# fp2.net
KiCad netlist of a schematic drawn in EAGLE
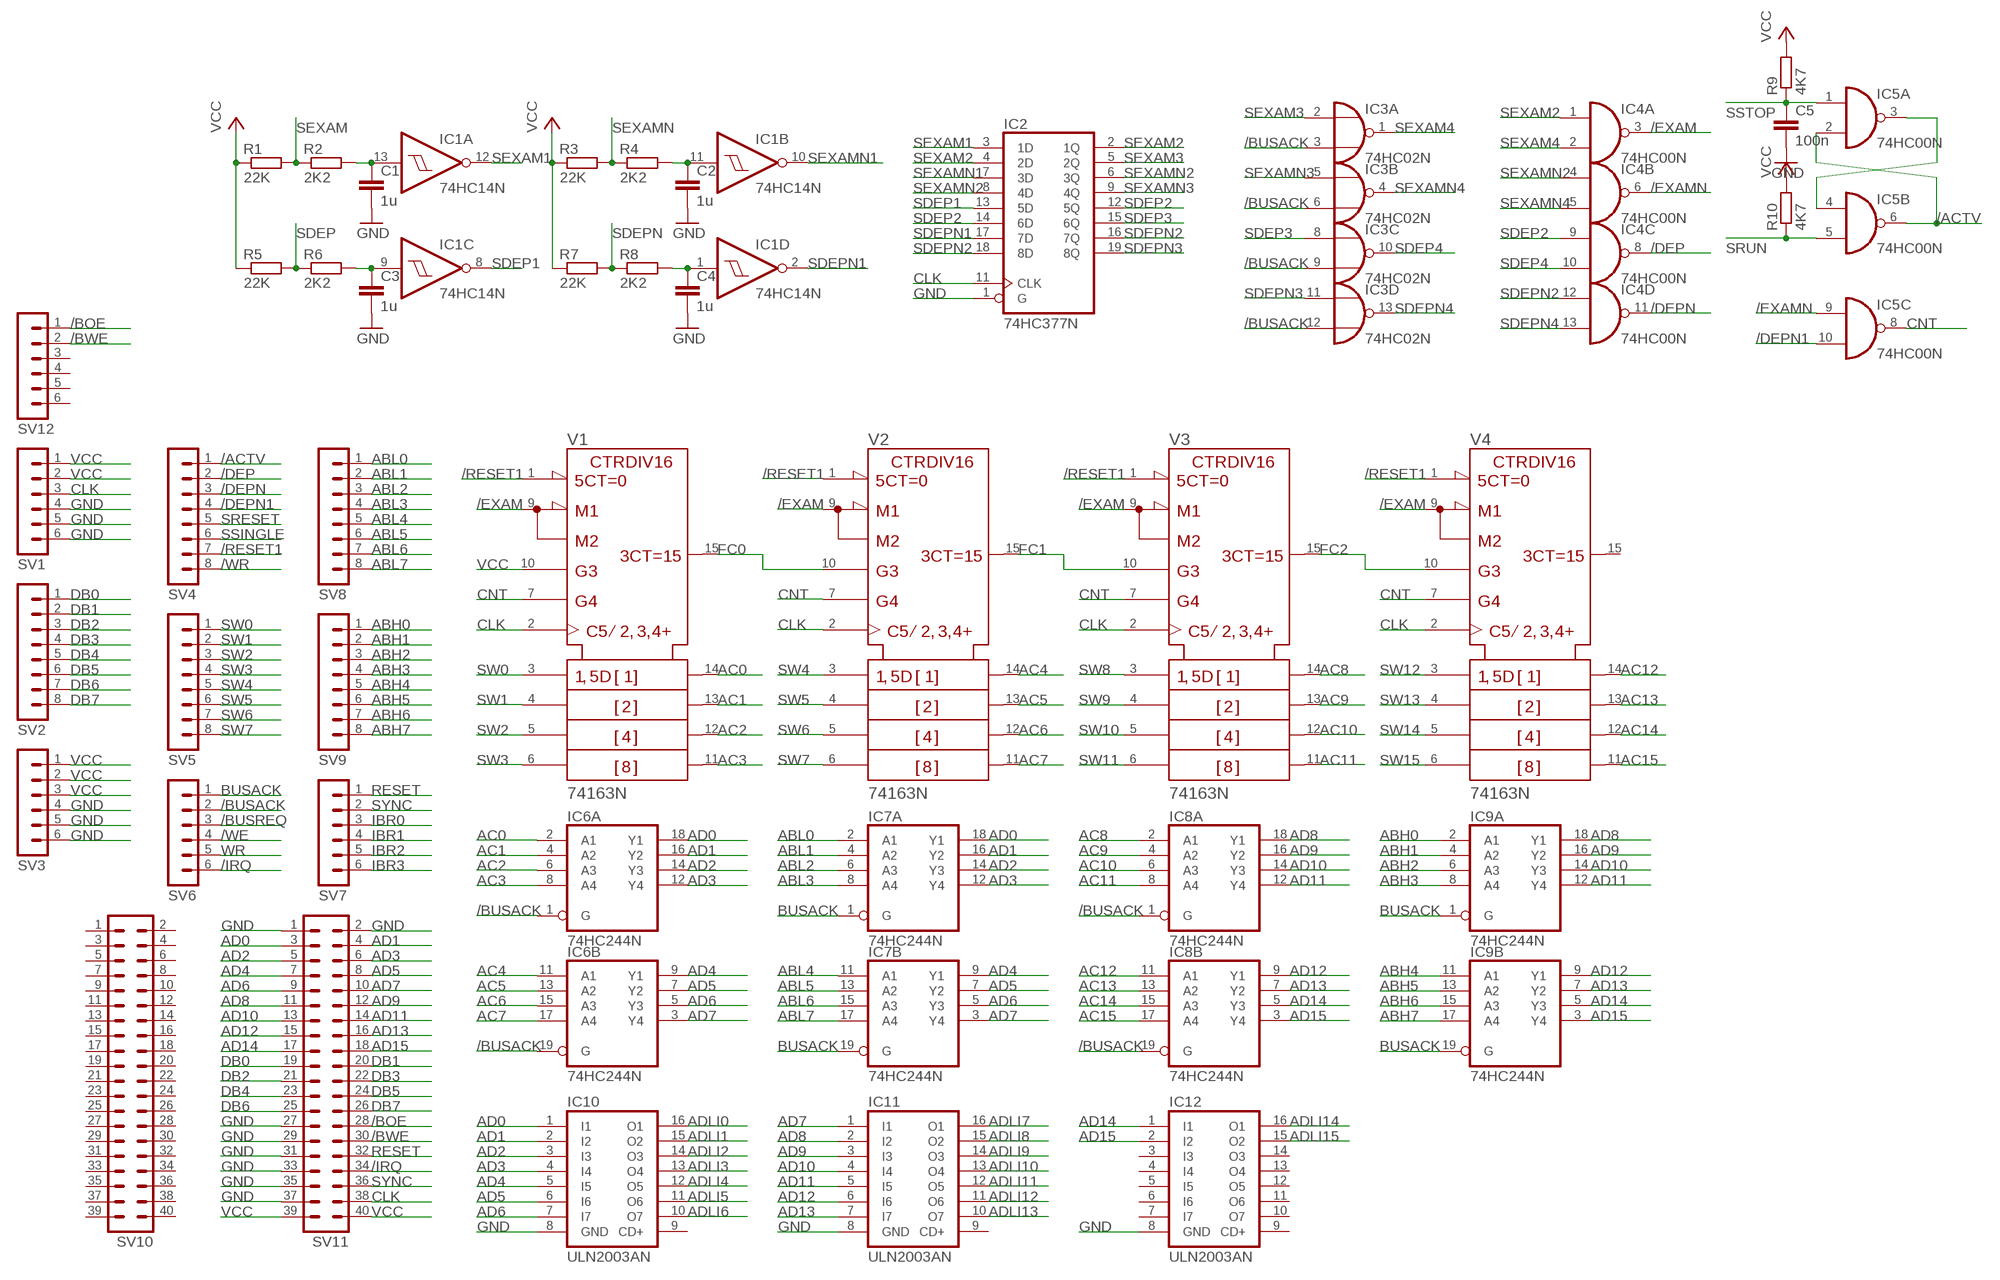
[diagram p0: schematic, sheet 1]

(export (version "E")
  (design (tool "Eeschema 10.0.6"))
  (components
    (comp (ref "C1")
      (value "1u")
      (footprint "eagle-import:C025-024X044")
      (libsource (lib "eagle-import") (part "C-EU025-024X044"))
    )
    (comp (ref "C2")
      (value "1u")
      (footprint "eagle-import:C025-024X044")
      (libsource (lib "eagle-import") (part "C-EU025-024X044"))
    )
    (comp (ref "C3")
      (value "1u")
      (footprint "eagle-import:C025-024X044")
      (libsource (lib "eagle-import") (part "C-EU025-024X044"))
    )
    (comp (ref "C4")
      (value "1u")
      (footprint "eagle-import:C025-024X044")
      (libsource (lib "eagle-import") (part "C-EU025-024X044"))
    )
    (comp (ref "C5")
      (value "100n")
      (footprint "eagle-import:C025-024X044")
      (libsource (lib "eagle-import") (part "C-EU025-024X044"))
    )
    (comp (ref "IC1")
      (value "74HC14N")
      (footprint "eagle-import:DIL14")
      (libsource (lib "eagle-import") (part "7414NHC"))
    )
    (comp (ref "IC2")
      (value "74HC377N")
      (footprint "eagle-import:DIL20")
      (libsource (lib "eagle-import") (part "74377NHC"))
    )
    (comp (ref "IC3")
      (value "74HC02N")
      (footprint "eagle-import:DIL14")
      (libsource (lib "eagle-import") (part "7402NHC"))
    )
    (comp (ref "IC4")
      (value "74HC00N")
      (footprint "eagle-import:DIL14")
      (libsource (lib "eagle-import") (part "7400NHC"))
    )
    (comp (ref "IC5")
      (value "74HC00N")
      (footprint "eagle-import:DIL14")
      (libsource (lib "eagle-import") (part "7400NHC"))
    )
    (comp (ref "IC6")
      (value "74HC244N")
      (footprint "eagle-import:DIL20")
      (libsource (lib "eagle-import") (part "74244NHC"))
    )
    (comp (ref "IC7")
      (value "74HC244N")
      (footprint "eagle-import:DIL20")
      (libsource (lib "eagle-import") (part "74244NHC"))
    )
    (comp (ref "IC8")
      (value "74HC244N")
      (footprint "eagle-import:DIL20")
      (libsource (lib "eagle-import") (part "74244NHC"))
    )
    (comp (ref "IC9")
      (value "74HC244N")
      (footprint "eagle-import:DIL20")
      (libsource (lib "eagle-import") (part "74244NHC"))
    )
    (comp (ref "IC10")
      (value "ULN2003AN")
      (footprint "eagle-import:DIL16")
      (libsource (lib "eagle-import") (part "ULN2003AN"))
    )
    (comp (ref "IC11")
      (value "ULN2003AN")
      (footprint "eagle-import:DIL16")
      (libsource (lib "eagle-import") (part "ULN2003AN"))
    )
    (comp (ref "IC12")
      (value "ULN2003AN")
      (footprint "eagle-import:DIL16")
      (libsource (lib "eagle-import") (part "ULN2003AN"))
    )
    (comp (ref "R1")
      (value "22K")
      (footprint "eagle-import:0204_7")
      (libsource (lib "eagle-import") (part "R-EU_0204/7"))
    )
    (comp (ref "R2")
      (value "2K2")
      (footprint "eagle-import:0204_7")
      (libsource (lib "eagle-import") (part "R-EU_0204/7"))
    )
    (comp (ref "R3")
      (value "22K")
      (footprint "eagle-import:0204_7")
      (libsource (lib "eagle-import") (part "R-EU_0204/7"))
    )
    (comp (ref "R4")
      (value "2K2")
      (footprint "eagle-import:0204_7")
      (libsource (lib "eagle-import") (part "R-EU_0204/7"))
    )
    (comp (ref "R5")
      (value "22K")
      (footprint "eagle-import:0204_7")
      (libsource (lib "eagle-import") (part "R-EU_0204/7"))
    )
    (comp (ref "R6")
      (value "2K2")
      (footprint "eagle-import:0204_7")
      (libsource (lib "eagle-import") (part "R-EU_0204/7"))
    )
    (comp (ref "R7")
      (value "22K")
      (footprint "eagle-import:0204_7")
      (libsource (lib "eagle-import") (part "R-EU_0204/7"))
    )
    (comp (ref "R8")
      (value "2K2")
      (footprint "eagle-import:0204_7")
      (libsource (lib "eagle-import") (part "R-EU_0204/7"))
    )
    (comp (ref "R9")
      (value "4K7")
      (footprint "eagle-import:0204_7")
      (libsource (lib "eagle-import") (part "R-EU_0204/7"))
    )
    (comp (ref "R10")
      (value "4K7")
      (footprint "eagle-import:0204_7")
      (libsource (lib "eagle-import") (part "R-EU_0204/7"))
    )
    (comp (ref "SV1")
      (value "MA06-1")
      (footprint "eagle-import:MA06-1")
      (libsource (lib "eagle-import") (part "MA06-1"))
    )
    (comp (ref "SV2")
      (value "MA08-1")
      (footprint "eagle-import:MA08-1")
      (libsource (lib "eagle-import") (part "MA08-1"))
    )
    (comp (ref "SV3")
      (value "MA06-1")
      (footprint "eagle-import:MA06-1")
      (libsource (lib "eagle-import") (part "MA06-1"))
    )
    (comp (ref "SV4")
      (value "MA08-1")
      (footprint "eagle-import:MA08-1")
      (libsource (lib "eagle-import") (part "MA08-1"))
    )
    (comp (ref "SV5")
      (value "MA08-1")
      (footprint "eagle-import:MA08-1")
      (libsource (lib "eagle-import") (part "MA08-1"))
    )
    (comp (ref "SV6")
      (value "MA06-1")
      (footprint "eagle-import:MA06-1")
      (libsource (lib "eagle-import") (part "MA06-1"))
    )
    (comp (ref "SV7")
      (value "MA06-1")
      (footprint "eagle-import:MA06-1")
      (libsource (lib "eagle-import") (part "MA06-1"))
    )
    (comp (ref "SV8")
      (value "MA08-1")
      (footprint "eagle-import:MA08-1")
      (libsource (lib "eagle-import") (part "MA08-1"))
    )
    (comp (ref "SV9")
      (value "MA08-1")
      (footprint "eagle-import:MA08-1")
      (libsource (lib "eagle-import") (part "MA08-1"))
    )
    (comp (ref "SV10")
      (value "MA20-2")
      (footprint "eagle-import:MA20-2")
      (libsource (lib "eagle-import") (part "MA20-2"))
    )
    (comp (ref "SV11")
      (value "MA20-2")
      (footprint "eagle-import:MA20-2")
      (libsource (lib "eagle-import") (part "MA20-2"))
    )
    (comp (ref "SV12")
      (value "MA06-1")
      (footprint "eagle-import:MA06-1")
      (libsource (lib "eagle-import") (part "MA06-1"))
    )
    (comp (ref "V1")
      (value "74163N")
      (footprint "eagle-import:DIL16")
      (libsource (lib "eagle-import") (part "74163N"))
    )
    (comp (ref "V2")
      (value "74163N")
      (footprint "eagle-import:DIL16")
      (libsource (lib "eagle-import") (part "74163N"))
    )
    (comp (ref "V3")
      (value "74163N")
      (footprint "eagle-import:DIL16")
      (libsource (lib "eagle-import") (part "74163N"))
    )
    (comp (ref "V4")
      (value "74163N")
      (footprint "eagle-import:DIL16")
      (libsource (lib "eagle-import") (part "74163N"))
    )
  )
  (nets
    (net (code "1") (name "/ABH0") (class "Default")
      (node (ref "IC9") (pin "2") (pinfunction "A1_2") (pintype "input"))
      (node (ref "SV9") (pin "1") (pinfunction "1_1") (pintype "passive"))
    )
    (net (code "2") (name "/ABH1") (class "Default")
      (node (ref "IC9") (pin "4") (pinfunction "A2_4") (pintype "input"))
      (node (ref "SV9") (pin "2") (pinfunction "2_2") (pintype "passive"))
    )
    (net (code "3") (name "/ABH2") (class "Default")
      (node (ref "IC9") (pin "6") (pinfunction "A3_6") (pintype "input"))
      (node (ref "SV9") (pin "3") (pinfunction "3_3") (pintype "passive"))
    )
    (net (code "4") (name "/ABH3") (class "Default")
      (node (ref "IC9") (pin "8") (pinfunction "A4_8") (pintype "input"))
      (node (ref "SV9") (pin "4") (pinfunction "4_4") (pintype "passive"))
    )
    (net (code "5") (name "/ABH4") (class "Default")
      (node (ref "IC9") (pin "11") (pinfunction "A1_11") (pintype "input"))
      (node (ref "SV9") (pin "5") (pinfunction "5_5") (pintype "passive"))
    )
    (net (code "6") (name "/ABH5") (class "Default")
      (node (ref "IC9") (pin "13") (pinfunction "A2_13") (pintype "input"))
      (node (ref "SV9") (pin "6") (pinfunction "6_6") (pintype "passive"))
    )
    (net (code "7") (name "/ABH6") (class "Default")
      (node (ref "IC9") (pin "15") (pinfunction "A3_15") (pintype "input"))
      (node (ref "SV9") (pin "7") (pinfunction "7_7") (pintype "passive"))
    )
    (net (code "8") (name "/ABH7") (class "Default")
      (node (ref "IC9") (pin "17") (pinfunction "A4_17") (pintype "input"))
      (node (ref "SV9") (pin "8") (pinfunction "8_8") (pintype "passive"))
    )
    (net (code "9") (name "/ABL0") (class "Default")
      (node (ref "IC7") (pin "2") (pinfunction "A1_2") (pintype "input"))
      (node (ref "SV8") (pin "1") (pinfunction "1_1") (pintype "passive"))
    )
    (net (code "10") (name "/ABL1") (class "Default")
      (node (ref "IC7") (pin "4") (pinfunction "A2_4") (pintype "input"))
      (node (ref "SV8") (pin "2") (pinfunction "2_2") (pintype "passive"))
    )
    (net (code "11") (name "/ABL2") (class "Default")
      (node (ref "IC7") (pin "6") (pinfunction "A3_6") (pintype "input"))
      (node (ref "SV8") (pin "3") (pinfunction "3_3") (pintype "passive"))
    )
    (net (code "12") (name "/ABL3") (class "Default")
      (node (ref "IC7") (pin "8") (pinfunction "A4_8") (pintype "input"))
      (node (ref "SV8") (pin "4") (pinfunction "4_4") (pintype "passive"))
    )
    (net (code "13") (name "/ABL4") (class "Default")
      (node (ref "IC7") (pin "11") (pinfunction "A1_11") (pintype "input"))
      (node (ref "SV8") (pin "5") (pinfunction "5_5") (pintype "passive"))
    )
    (net (code "14") (name "/ABL5") (class "Default")
      (node (ref "IC7") (pin "13") (pinfunction "A2_13") (pintype "input"))
      (node (ref "SV8") (pin "6") (pinfunction "6_6") (pintype "passive"))
    )
    (net (code "15") (name "/ABL6") (class "Default")
      (node (ref "IC7") (pin "15") (pinfunction "A3_15") (pintype "input"))
      (node (ref "SV8") (pin "7") (pinfunction "7_7") (pintype "passive"))
    )
    (net (code "16") (name "/ABL7") (class "Default")
      (node (ref "IC7") (pin "17") (pinfunction "A4_17") (pintype "input"))
      (node (ref "SV8") (pin "8") (pinfunction "8_8") (pintype "passive"))
    )
    (net (code "17") (name "/AC0") (class "Default")
      (node (ref "IC6") (pin "2") (pinfunction "A1_2") (pintype "input"))
      (node (ref "V1") (pin "14") (pinfunction "QA_14") (pintype "output"))
    )
    (net (code "18") (name "/AC1") (class "Default")
      (node (ref "IC6") (pin "4") (pinfunction "A2_4") (pintype "input"))
      (node (ref "V1") (pin "13") (pinfunction "QB_13") (pintype "output"))
    )
    (net (code "19") (name "/AC2") (class "Default")
      (node (ref "IC6") (pin "6") (pinfunction "A3_6") (pintype "input"))
      (node (ref "V1") (pin "12") (pinfunction "QC_12") (pintype "output"))
    )
    (net (code "20") (name "/AC3") (class "Default")
      (node (ref "IC6") (pin "8") (pinfunction "A4_8") (pintype "input"))
      (node (ref "V1") (pin "11") (pinfunction "QD_11") (pintype "output"))
    )
    (net (code "21") (name "/AC4") (class "Default")
      (node (ref "IC6") (pin "11") (pinfunction "A1_11") (pintype "input"))
      (node (ref "V2") (pin "14") (pinfunction "QA_14") (pintype "output"))
    )
    (net (code "22") (name "/AC5") (class "Default")
      (node (ref "IC6") (pin "13") (pinfunction "A2_13") (pintype "input"))
      (node (ref "V2") (pin "13") (pinfunction "QB_13") (pintype "output"))
    )
    (net (code "23") (name "/AC6") (class "Default")
      (node (ref "IC6") (pin "15") (pinfunction "A3_15") (pintype "input"))
      (node (ref "V2") (pin "12") (pinfunction "QC_12") (pintype "output"))
    )
    (net (code "24") (name "/AC7") (class "Default")
      (node (ref "IC6") (pin "17") (pinfunction "A4_17") (pintype "input"))
      (node (ref "V2") (pin "11") (pinfunction "QD_11") (pintype "output"))
    )
    (net (code "25") (name "/AC8") (class "Default")
      (node (ref "IC8") (pin "2") (pinfunction "A1_2") (pintype "input"))
      (node (ref "V3") (pin "14") (pinfunction "QA_14") (pintype "output"))
    )
    (net (code "26") (name "/AC9") (class "Default")
      (node (ref "IC8") (pin "4") (pinfunction "A2_4") (pintype "input"))
      (node (ref "V3") (pin "13") (pinfunction "QB_13") (pintype "output"))
    )
    (net (code "27") (name "/AC10") (class "Default")
      (node (ref "IC8") (pin "6") (pinfunction "A3_6") (pintype "input"))
      (node (ref "V3") (pin "12") (pinfunction "QC_12") (pintype "output"))
    )
    (net (code "28") (name "/AC11") (class "Default")
      (node (ref "IC8") (pin "8") (pinfunction "A4_8") (pintype "input"))
      (node (ref "V3") (pin "11") (pinfunction "QD_11") (pintype "output"))
    )
    (net (code "29") (name "/AC12") (class "Default")
      (node (ref "IC8") (pin "11") (pinfunction "A1_11") (pintype "input"))
      (node (ref "V4") (pin "14") (pinfunction "QA_14") (pintype "output"))
    )
    (net (code "30") (name "/AC13") (class "Default")
      (node (ref "IC8") (pin "13") (pinfunction "A2_13") (pintype "input"))
      (node (ref "V4") (pin "13") (pinfunction "QB_13") (pintype "output"))
    )
    (net (code "31") (name "/AC14") (class "Default")
      (node (ref "IC8") (pin "15") (pinfunction "A3_15") (pintype "input"))
      (node (ref "V4") (pin "12") (pinfunction "QC_12") (pintype "output"))
    )
    (net (code "32") (name "/AC15") (class "Default")
      (node (ref "IC8") (pin "17") (pinfunction "A4_17") (pintype "input"))
      (node (ref "V4") (pin "11") (pinfunction "QD_11") (pintype "output"))
    )
    (net (code "33") (name "/AD0") (class "Default")
      (node (ref "IC10") (pin "1") (pinfunction "I1_1") (pintype "input"))
      (node (ref "IC6") (pin "18") (pinfunction "Y1_18") (pintype "tri_state"))
      (node (ref "IC7") (pin "18") (pinfunction "Y1_18") (pintype "tri_state"))
      (node (ref "SV11") (pin "3") (pinfunction "3_3") (pintype "passive"))
    )
    (net (code "34") (name "/AD1") (class "Default")
      (node (ref "IC10") (pin "2") (pinfunction "I2_2") (pintype "input"))
      (node (ref "IC6") (pin "16") (pinfunction "Y2_16") (pintype "tri_state"))
      (node (ref "IC7") (pin "16") (pinfunction "Y2_16") (pintype "tri_state"))
      (node (ref "SV11") (pin "4") (pinfunction "4_4") (pintype "passive"))
    )
    (net (code "35") (name "/AD2") (class "Default")
      (node (ref "IC10") (pin "3") (pinfunction "I3_3") (pintype "input"))
      (node (ref "IC6") (pin "14") (pinfunction "Y3_14") (pintype "tri_state"))
      (node (ref "IC7") (pin "14") (pinfunction "Y3_14") (pintype "tri_state"))
      (node (ref "SV11") (pin "5") (pinfunction "5_5") (pintype "passive"))
    )
    (net (code "36") (name "/AD3") (class "Default")
      (node (ref "IC10") (pin "4") (pinfunction "I4_4") (pintype "input"))
      (node (ref "IC6") (pin "12") (pinfunction "Y4_12") (pintype "tri_state"))
      (node (ref "IC7") (pin "12") (pinfunction "Y4_12") (pintype "tri_state"))
      (node (ref "SV11") (pin "6") (pinfunction "6_6") (pintype "passive"))
    )
    (net (code "37") (name "/AD4") (class "Default")
      (node (ref "IC10") (pin "5") (pinfunction "I5_5") (pintype "input"))
      (node (ref "IC6") (pin "9") (pinfunction "Y1_9") (pintype "tri_state"))
      (node (ref "IC7") (pin "9") (pinfunction "Y1_9") (pintype "tri_state"))
      (node (ref "SV11") (pin "7") (pinfunction "7_7") (pintype "passive"))
    )
    (net (code "38") (name "/AD5") (class "Default")
      (node (ref "IC10") (pin "6") (pinfunction "I6_6") (pintype "input"))
      (node (ref "IC6") (pin "7") (pinfunction "Y2_7") (pintype "tri_state"))
      (node (ref "IC7") (pin "7") (pinfunction "Y2_7") (pintype "tri_state"))
      (node (ref "SV11") (pin "8") (pinfunction "8_8") (pintype "passive"))
    )
    (net (code "39") (name "/AD6") (class "Default")
      (node (ref "IC10") (pin "7") (pinfunction "I7_7") (pintype "input"))
      (node (ref "IC6") (pin "5") (pinfunction "Y3_5") (pintype "tri_state"))
      (node (ref "IC7") (pin "5") (pinfunction "Y3_5") (pintype "tri_state"))
      (node (ref "SV11") (pin "9") (pinfunction "9_9") (pintype "passive"))
    )
    (net (code "40") (name "/AD7") (class "Default")
      (node (ref "IC11") (pin "1") (pinfunction "I1_1") (pintype "input"))
      (node (ref "IC6") (pin "3") (pinfunction "Y4_3") (pintype "tri_state"))
      (node (ref "IC7") (pin "3") (pinfunction "Y4_3") (pintype "tri_state"))
      (node (ref "SV11") (pin "10") (pinfunction "10_10") (pintype "passive"))
    )
    (net (code "41") (name "/AD8") (class "Default")
      (node (ref "IC11") (pin "2") (pinfunction "I2_2") (pintype "input"))
      (node (ref "IC8") (pin "18") (pinfunction "Y1_18") (pintype "tri_state"))
      (node (ref "IC9") (pin "18") (pinfunction "Y1_18") (pintype "tri_state"))
      (node (ref "SV11") (pin "11") (pinfunction "11_11") (pintype "passive"))
    )
    (net (code "42") (name "/AD9") (class "Default")
      (node (ref "IC11") (pin "3") (pinfunction "I3_3") (pintype "input"))
      (node (ref "IC8") (pin "16") (pinfunction "Y2_16") (pintype "tri_state"))
      (node (ref "IC9") (pin "16") (pinfunction "Y2_16") (pintype "tri_state"))
      (node (ref "SV11") (pin "12") (pinfunction "12_12") (pintype "passive"))
    )
    (net (code "43") (name "/AD10") (class "Default")
      (node (ref "IC11") (pin "4") (pinfunction "I4_4") (pintype "input"))
      (node (ref "IC8") (pin "14") (pinfunction "Y3_14") (pintype "tri_state"))
      (node (ref "IC9") (pin "14") (pinfunction "Y3_14") (pintype "tri_state"))
      (node (ref "SV11") (pin "13") (pinfunction "13_13") (pintype "passive"))
    )
    (net (code "44") (name "/AD11") (class "Default")
      (node (ref "IC11") (pin "5") (pinfunction "I5_5") (pintype "input"))
      (node (ref "IC8") (pin "12") (pinfunction "Y4_12") (pintype "tri_state"))
      (node (ref "IC9") (pin "12") (pinfunction "Y4_12") (pintype "tri_state"))
      (node (ref "SV11") (pin "14") (pinfunction "14_14") (pintype "passive"))
    )
    (net (code "45") (name "/AD12") (class "Default")
      (node (ref "IC11") (pin "6") (pinfunction "I6_6") (pintype "input"))
      (node (ref "IC8") (pin "9") (pinfunction "Y1_9") (pintype "tri_state"))
      (node (ref "IC9") (pin "9") (pinfunction "Y1_9") (pintype "tri_state"))
      (node (ref "SV11") (pin "15") (pinfunction "15_15") (pintype "passive"))
    )
    (net (code "46") (name "/AD13") (class "Default")
      (node (ref "IC11") (pin "7") (pinfunction "I7_7") (pintype "input"))
      (node (ref "IC8") (pin "7") (pinfunction "Y2_7") (pintype "tri_state"))
      (node (ref "IC9") (pin "7") (pinfunction "Y2_7") (pintype "tri_state"))
      (node (ref "SV11") (pin "16") (pinfunction "16_16") (pintype "passive"))
    )
    (net (code "47") (name "/AD14") (class "Default")
      (node (ref "IC12") (pin "1") (pinfunction "I1_1") (pintype "input"))
      (node (ref "IC8") (pin "5") (pinfunction "Y3_5") (pintype "tri_state"))
      (node (ref "IC9") (pin "5") (pinfunction "Y3_5") (pintype "tri_state"))
      (node (ref "SV11") (pin "17") (pinfunction "17_17") (pintype "passive"))
    )
    (net (code "48") (name "/AD15") (class "Default")
      (node (ref "IC12") (pin "2") (pinfunction "I2_2") (pintype "input"))
      (node (ref "IC8") (pin "3") (pinfunction "Y4_3") (pintype "tri_state"))
      (node (ref "IC9") (pin "3") (pinfunction "Y4_3") (pintype "tri_state"))
      (node (ref "SV11") (pin "18") (pinfunction "18_18") (pintype "passive"))
    )
    (net (code "49") (name "/ADLI0") (class "Default")
      (node (ref "IC10") (pin "16") (pinfunction "O1_16") (pintype "open_collector"))
    )
    (net (code "50") (name "/ADLI1") (class "Default")
      (node (ref "IC10") (pin "15") (pinfunction "O2_15") (pintype "open_collector"))
    )
    (net (code "51") (name "/ADLI2") (class "Default")
      (node (ref "IC10") (pin "14") (pinfunction "O3_14") (pintype "open_collector"))
    )
    (net (code "52") (name "/ADLI3") (class "Default")
      (node (ref "IC10") (pin "13") (pinfunction "O4_13") (pintype "open_collector"))
    )
    (net (code "53") (name "/ADLI4") (class "Default")
      (node (ref "IC10") (pin "12") (pinfunction "O5_12") (pintype "open_collector"))
    )
    (net (code "54") (name "/ADLI5") (class "Default")
      (node (ref "IC10") (pin "11") (pinfunction "O6_11") (pintype "open_collector"))
    )
    (net (code "55") (name "/ADLI6") (class "Default")
      (node (ref "IC10") (pin "10") (pinfunction "O7_10") (pintype "open_collector"))
    )
    (net (code "56") (name "/ADLI7") (class "Default")
      (node (ref "IC11") (pin "16") (pinfunction "O1_16") (pintype "open_collector"))
    )
    (net (code "57") (name "/ADLI8") (class "Default")
      (node (ref "IC11") (pin "15") (pinfunction "O2_15") (pintype "open_collector"))
    )
    (net (code "58") (name "/ADLI9") (class "Default")
      (node (ref "IC11") (pin "14") (pinfunction "O3_14") (pintype "open_collector"))
    )
    (net (code "59") (name "/ADLI10") (class "Default")
      (node (ref "IC11") (pin "13") (pinfunction "O4_13") (pintype "open_collector"))
    )
    (net (code "60") (name "/ADLI11") (class "Default")
      (node (ref "IC11") (pin "12") (pinfunction "O5_12") (pintype "open_collector"))
    )
    (net (code "61") (name "/ADLI12") (class "Default")
      (node (ref "IC11") (pin "11") (pinfunction "O6_11") (pintype "open_collector"))
    )
    (net (code "62") (name "/ADLI13") (class "Default")
      (node (ref "IC11") (pin "10") (pinfunction "O7_10") (pintype "open_collector"))
    )
    (net (code "63") (name "/ADLI14") (class "Default")
      (node (ref "IC12") (pin "16") (pinfunction "O1_16") (pintype "open_collector"))
    )
    (net (code "64") (name "/ADLI15") (class "Default")
      (node (ref "IC12") (pin "15") (pinfunction "O2_15") (pintype "open_collector"))
    )
    (net (code "65") (name "/BUSACK") (class "Default")
      (node (ref "IC7") (pin "1") (pinfunction "G_1") (pintype "input"))
      (node (ref "IC7") (pin "19") (pinfunction "G_19") (pintype "input"))
      (node (ref "IC9") (pin "1") (pinfunction "G_1") (pintype "input"))
      (node (ref "IC9") (pin "19") (pinfunction "G_19") (pintype "input"))
      (node (ref "SV6") (pin "1") (pinfunction "1_1") (pintype "passive"))
    )
    (net (code "66") (name "/CLK") (class "Default")
      (node (ref "IC2") (pin "11") (pinfunction "CLK_11") (pintype "input"))
      (node (ref "SV1") (pin "3") (pinfunction "3_3") (pintype "passive"))
      (node (ref "SV11") (pin "38") (pinfunction "38_38") (pintype "passive"))
      (node (ref "V1") (pin "2") (pinfunction "CLK_2") (pintype "input"))
      (node (ref "V2") (pin "2") (pinfunction "CLK_2") (pintype "input"))
      (node (ref "V3") (pin "2") (pinfunction "CLK_2") (pintype "input"))
      (node (ref "V4") (pin "2") (pinfunction "CLK_2") (pintype "input"))
    )
    (net (code "67") (name "/CNT") (class "Default")
      (node (ref "IC5") (pin "8") (pinfunction "O_8") (pintype "output"))
      (node (ref "V1") (pin "7") (pinfunction "ENP_7") (pintype "input"))
      (node (ref "V2") (pin "7") (pinfunction "ENP_7") (pintype "input"))
      (node (ref "V3") (pin "7") (pinfunction "ENP_7") (pintype "input"))
      (node (ref "V4") (pin "7") (pinfunction "ENP_7") (pintype "input"))
    )
    (net (code "68") (name "/DB0") (class "Default")
      (node (ref "SV11") (pin "19") (pinfunction "19_19") (pintype "passive"))
      (node (ref "SV2") (pin "1") (pinfunction "1_1") (pintype "passive"))
    )
    (net (code "69") (name "/DB1") (class "Default")
      (node (ref "SV11") (pin "20") (pinfunction "20_20") (pintype "passive"))
      (node (ref "SV2") (pin "2") (pinfunction "2_2") (pintype "passive"))
    )
    (net (code "70") (name "/DB2") (class "Default")
      (node (ref "SV11") (pin "21") (pinfunction "21_21") (pintype "passive"))
      (node (ref "SV2") (pin "3") (pinfunction "3_3") (pintype "passive"))
    )
    (net (code "71") (name "/DB3") (class "Default")
      (node (ref "SV11") (pin "22") (pinfunction "22_22") (pintype "passive"))
      (node (ref "SV2") (pin "4") (pinfunction "4_4") (pintype "passive"))
    )
    (net (code "72") (name "/DB4") (class "Default")
      (node (ref "SV11") (pin "23") (pinfunction "23_23") (pintype "passive"))
      (node (ref "SV2") (pin "5") (pinfunction "5_5") (pintype "passive"))
    )
    (net (code "73") (name "/DB5") (class "Default")
      (node (ref "SV11") (pin "24") (pinfunction "24_24") (pintype "passive"))
      (node (ref "SV2") (pin "6") (pinfunction "6_6") (pintype "passive"))
    )
    (net (code "74") (name "/DB6") (class "Default")
      (node (ref "SV11") (pin "25") (pinfunction "25_25") (pintype "passive"))
      (node (ref "SV2") (pin "7") (pinfunction "7_7") (pintype "passive"))
    )
    (net (code "75") (name "/DB7") (class "Default")
      (node (ref "SV11") (pin "26") (pinfunction "26_26") (pintype "passive"))
      (node (ref "SV2") (pin "8") (pinfunction "8_8") (pintype "passive"))
    )
    (net (code "76") (name "/FC0") (class "Default")
      (node (ref "V1") (pin "15") (pinfunction "RCO_15") (pintype "output"))
      (node (ref "V2") (pin "10") (pinfunction "ENT_10") (pintype "input"))
    )
    (net (code "77") (name "/FC1") (class "Default")
      (node (ref "V2") (pin "15") (pinfunction "RCO_15") (pintype "output"))
      (node (ref "V3") (pin "10") (pinfunction "ENT_10") (pintype "input"))
    )
    (net (code "78") (name "/FC2") (class "Default")
      (node (ref "V3") (pin "15") (pinfunction "RCO_15") (pintype "output"))
      (node (ref "V4") (pin "10") (pinfunction "ENT_10") (pintype "input"))
    )
    (net (code "79") (name "/IBR0") (class "Default")
      (node (ref "SV7") (pin "3") (pinfunction "3_3") (pintype "passive"))
    )
    (net (code "80") (name "/IBR1") (class "Default")
      (node (ref "SV7") (pin "4") (pinfunction "4_4") (pintype "passive"))
    )
    (net (code "81") (name "/IBR2") (class "Default")
      (node (ref "SV7") (pin "5") (pinfunction "5_5") (pintype "passive"))
    )
    (net (code "82") (name "/IBR3") (class "Default")
      (node (ref "SV7") (pin "6") (pinfunction "6_6") (pintype "passive"))
    )
    (net (code "83") (name "/RESET") (class "Default")
      (node (ref "SV11") (pin "32") (pinfunction "32_32") (pintype "passive"))
      (node (ref "SV7") (pin "1") (pinfunction "1_1") (pintype "passive"))
    )
    (net (code "84") (name "/SDEP") (class "Default")
      (node (ref "R5") (pin "2") (pinfunction "2_2") (pintype "passive"))
      (node (ref "R6") (pin "1") (pinfunction "1_1") (pintype "passive"))
    )
    (net (code "85") (name "/SDEP1") (class "Default")
      (node (ref "IC1") (pin "8") (pinfunction "O_8") (pintype "output"))
      (node (ref "IC2") (pin "13") (pinfunction "5D_13") (pintype "input"))
    )
    (net (code "86") (name "/SDEP2") (class "Default")
      (node (ref "IC2") (pin "12") (pinfunction "5Q_12") (pintype "output"))
      (node (ref "IC2") (pin "14") (pinfunction "6D_14") (pintype "input"))
      (node (ref "IC4") (pin "9") (pinfunction "I0_9") (pintype "input"))
    )
    (net (code "87") (name "/SDEP3") (class "Default")
      (node (ref "IC2") (pin "15") (pinfunction "6Q_15") (pintype "output"))
      (node (ref "IC3") (pin "8") (pinfunction "I0_8") (pintype "input"))
    )
    (net (code "88") (name "/SDEP4") (class "Default")
      (node (ref "IC3") (pin "10") (pinfunction "O_10") (pintype "output"))
      (node (ref "IC4") (pin "10") (pinfunction "I1_10") (pintype "input"))
    )
    (net (code "89") (name "/SDEPN") (class "Default")
      (node (ref "R7") (pin "2") (pinfunction "2_2") (pintype "passive"))
      (node (ref "R8") (pin "1") (pinfunction "1_1") (pintype "passive"))
    )
    (net (code "90") (name "/SDEPN1") (class "Default")
      (node (ref "IC1") (pin "2") (pinfunction "O_2") (pintype "output"))
      (node (ref "IC2") (pin "17") (pinfunction "7D_17") (pintype "input"))
    )
    (net (code "91") (name "/SDEPN2") (class "Default")
      (node (ref "IC2") (pin "16") (pinfunction "7Q_16") (pintype "output"))
      (node (ref "IC2") (pin "18") (pinfunction "8D_18") (pintype "input"))
      (node (ref "IC4") (pin "12") (pinfunction "I0_12") (pintype "input"))
    )
    (net (code "92") (name "/SDEPN3") (class "Default")
      (node (ref "IC2") (pin "19") (pinfunction "8Q_19") (pintype "output"))
      (node (ref "IC3") (pin "11") (pinfunction "I0_11") (pintype "input"))
    )
    (net (code "93") (name "/SDEPN4") (class "Default")
      (node (ref "IC3") (pin "13") (pinfunction "O_13") (pintype "output"))
      (node (ref "IC4") (pin "13") (pinfunction "I1_13") (pintype "input"))
    )
    (net (code "94") (name "/SEXAM") (class "Default")
      (node (ref "R1") (pin "2") (pinfunction "2_2") (pintype "passive"))
      (node (ref "R2") (pin "1") (pinfunction "1_1") (pintype "passive"))
    )
    (net (code "95") (name "/SEXAM1") (class "Default")
      (node (ref "IC1") (pin "12") (pinfunction "O_12") (pintype "output"))
      (node (ref "IC2") (pin "3") (pinfunction "1D_3") (pintype "input"))
    )
    (net (code "96") (name "/SEXAM2") (class "Default")
      (node (ref "IC2") (pin "2") (pinfunction "1Q_2") (pintype "output"))
      (node (ref "IC2") (pin "4") (pinfunction "2D_4") (pintype "input"))
      (node (ref "IC4") (pin "1") (pinfunction "I0_1") (pintype "input"))
    )
    (net (code "97") (name "/SEXAM3") (class "Default")
      (node (ref "IC2") (pin "5") (pinfunction "2Q_5") (pintype "output"))
      (node (ref "IC3") (pin "2") (pinfunction "I0_2") (pintype "input"))
    )
    (net (code "98") (name "/SEXAM4") (class "Default")
      (node (ref "IC3") (pin "1") (pinfunction "O_1") (pintype "output"))
      (node (ref "IC4") (pin "2") (pinfunction "I1_2") (pintype "input"))
    )
    (net (code "99") (name "/SEXAMN") (class "Default")
      (node (ref "R3") (pin "2") (pinfunction "2_2") (pintype "passive"))
      (node (ref "R4") (pin "1") (pinfunction "1_1") (pintype "passive"))
    )
    (net (code "100") (name "/SEXAMN1") (class "Default")
      (node (ref "IC1") (pin "10") (pinfunction "O_10") (pintype "output"))
      (node (ref "IC2") (pin "7") (pinfunction "3D_7") (pintype "input"))
    )
    (net (code "101") (name "/SEXAMN2") (class "Default")
      (node (ref "IC2") (pin "6") (pinfunction "3Q_6") (pintype "output"))
      (node (ref "IC2") (pin "8") (pinfunction "4D_8") (pintype "input"))
      (node (ref "IC4") (pin "4") (pinfunction "I0_4") (pintype "input"))
    )
    (net (code "102") (name "/SEXAMN3") (class "Default")
      (node (ref "IC2") (pin "9") (pinfunction "4Q_9") (pintype "output"))
      (node (ref "IC3") (pin "5") (pinfunction "I0_5") (pintype "input"))
    )
    (net (code "103") (name "/SEXAMN4") (class "Default")
      (node (ref "IC3") (pin "4") (pinfunction "O_4") (pintype "output"))
      (node (ref "IC4") (pin "5") (pinfunction "I1_5") (pintype "input"))
    )
    (net (code "104") (name "/SRESET") (class "Default")
      (node (ref "SV4") (pin "5") (pinfunction "5_5") (pintype "passive"))
    )
    (net (code "105") (name "/SRUN") (class "Default")
      (node (ref "IC5") (pin "5") (pinfunction "I1_5") (pintype "input"))
      (node (ref "R10") (pin "1") (pinfunction "1_1") (pintype "passive"))
    )
    (net (code "106") (name "/SSINGLE") (class "Default")
      (node (ref "SV4") (pin "6") (pinfunction "6_6") (pintype "passive"))
    )
    (net (code "107") (name "/SSTOP") (class "Default")
      (node (ref "C5") (pin "1") (pinfunction "1_1") (pintype "passive"))
      (node (ref "IC5") (pin "1") (pinfunction "I0_1") (pintype "input"))
      (node (ref "R9") (pin "1") (pinfunction "1_1") (pintype "passive"))
    )
    (net (code "108") (name "/SW0") (class "Default")
      (node (ref "SV5") (pin "1") (pinfunction "1_1") (pintype "passive"))
      (node (ref "V1") (pin "3") (pinfunction "A_3") (pintype "input"))
    )
    (net (code "109") (name "/SW1") (class "Default")
      (node (ref "SV5") (pin "2") (pinfunction "2_2") (pintype "passive"))
      (node (ref "V1") (pin "4") (pinfunction "B_4") (pintype "input"))
    )
    (net (code "110") (name "/SW2") (class "Default")
      (node (ref "SV5") (pin "3") (pinfunction "3_3") (pintype "passive"))
      (node (ref "V1") (pin "5") (pinfunction "C_5") (pintype "input"))
    )
    (net (code "111") (name "/SW3") (class "Default")
      (node (ref "SV5") (pin "4") (pinfunction "4_4") (pintype "passive"))
      (node (ref "V1") (pin "6") (pinfunction "D_6") (pintype "input"))
    )
    (net (code "112") (name "/SW4") (class "Default")
      (node (ref "SV5") (pin "5") (pinfunction "5_5") (pintype "passive"))
      (node (ref "V2") (pin "3") (pinfunction "A_3") (pintype "input"))
    )
    (net (code "113") (name "/SW5") (class "Default")
      (node (ref "SV5") (pin "6") (pinfunction "6_6") (pintype "passive"))
      (node (ref "V2") (pin "4") (pinfunction "B_4") (pintype "input"))
    )
    (net (code "114") (name "/SW6") (class "Default")
      (node (ref "SV5") (pin "7") (pinfunction "7_7") (pintype "passive"))
      (node (ref "V2") (pin "5") (pinfunction "C_5") (pintype "input"))
    )
    (net (code "115") (name "/SW7") (class "Default")
      (node (ref "SV5") (pin "8") (pinfunction "8_8") (pintype "passive"))
      (node (ref "V2") (pin "6") (pinfunction "D_6") (pintype "input"))
    )
    (net (code "116") (name "/SW8") (class "Default")
      (node (ref "V3") (pin "3") (pinfunction "A_3") (pintype "input"))
    )
    (net (code "117") (name "/SW9") (class "Default")
      (node (ref "V3") (pin "4") (pinfunction "B_4") (pintype "input"))
    )
    (net (code "118") (name "/SW10") (class "Default")
      (node (ref "V3") (pin "5") (pinfunction "C_5") (pintype "input"))
    )
    (net (code "119") (name "/SW11") (class "Default")
      (node (ref "V3") (pin "6") (pinfunction "D_6") (pintype "input"))
    )
    (net (code "120") (name "/SW12") (class "Default")
      (node (ref "V4") (pin "3") (pinfunction "A_3") (pintype "input"))
    )
    (net (code "121") (name "/SW13") (class "Default")
      (node (ref "V4") (pin "4") (pinfunction "B_4") (pintype "input"))
    )
    (net (code "122") (name "/SW14") (class "Default")
      (node (ref "V4") (pin "5") (pinfunction "C_5") (pintype "input"))
    )
    (net (code "123") (name "/SW15") (class "Default")
      (node (ref "V4") (pin "6") (pinfunction "D_6") (pintype "input"))
    )
    (net (code "124") (name "/SYNC") (class "Default")
      (node (ref "SV11") (pin "36") (pinfunction "36_36") (pintype "passive"))
      (node (ref "SV7") (pin "2") (pinfunction "2_2") (pintype "passive"))
    )
    (net (code "125") (name "/WR") (class "Default")
      (node (ref "SV6") (pin "5") (pinfunction "5_5") (pintype "passive"))
    )
    (net (code "126") (name "/{slash}ACTV") (class "Default")
      (node (ref "IC5") (pin "2") (pinfunction "I1_2") (pintype "input"))
      (node (ref "IC5") (pin "6") (pinfunction "O_6") (pintype "output"))
      (node (ref "SV4") (pin "1") (pinfunction "1_1") (pintype "passive"))
    )
    (net (code "127") (name "/{slash}BOE") (class "Default")
      (node (ref "SV11") (pin "28") (pinfunction "28_28") (pintype "passive"))
      (node (ref "SV12") (pin "1") (pinfunction "1_1") (pintype "passive"))
    )
    (net (code "128") (name "/{slash}BUSACK") (class "Default")
      (node (ref "IC3") (pin "12") (pinfunction "I1_12") (pintype "input"))
      (node (ref "IC3") (pin "3") (pinfunction "I1_3") (pintype "input"))
      (node (ref "IC3") (pin "6") (pinfunction "I1_6") (pintype "input"))
      (node (ref "IC3") (pin "9") (pinfunction "I1_9") (pintype "input"))
      (node (ref "IC6") (pin "1") (pinfunction "G_1") (pintype "input"))
      (node (ref "IC6") (pin "19") (pinfunction "G_19") (pintype "input"))
      (node (ref "IC8") (pin "1") (pinfunction "G_1") (pintype "input"))
      (node (ref "IC8") (pin "19") (pinfunction "G_19") (pintype "input"))
      (node (ref "SV6") (pin "2") (pinfunction "2_2") (pintype "passive"))
    )
    (net (code "129") (name "/{slash}BUSREQ") (class "Default")
      (node (ref "SV6") (pin "3") (pinfunction "3_3") (pintype "passive"))
    )
    (net (code "130") (name "/{slash}BWE") (class "Default")
      (node (ref "SV11") (pin "30") (pinfunction "30_30") (pintype "passive"))
      (node (ref "SV12") (pin "2") (pinfunction "2_2") (pintype "passive"))
    )
    (net (code "131") (name "/{slash}DEP") (class "Default")
      (node (ref "IC4") (pin "8") (pinfunction "O_8") (pintype "output"))
      (node (ref "SV4") (pin "2") (pinfunction "2_2") (pintype "passive"))
    )
    (net (code "132") (name "/{slash}DEPN") (class "Default")
      (node (ref "IC4") (pin "11") (pinfunction "O_11") (pintype "output"))
      (node (ref "SV4") (pin "3") (pinfunction "3_3") (pintype "passive"))
    )
    (net (code "133") (name "/{slash}DEPN1") (class "Default")
      (node (ref "IC5") (pin "10") (pinfunction "I1_10") (pintype "input"))
      (node (ref "SV4") (pin "4") (pinfunction "4_4") (pintype "passive"))
    )
    (net (code "134") (name "/{slash}EXAM") (class "Default")
      (node (ref "IC4") (pin "3") (pinfunction "O_3") (pintype "output"))
      (node (ref "V1") (pin "9") (pinfunction "~{LOAD}_9") (pintype "input"))
      (node (ref "V2") (pin "9") (pinfunction "~{LOAD}_9") (pintype "input"))
      (node (ref "V3") (pin "9") (pinfunction "~{LOAD}_9") (pintype "input"))
      (node (ref "V4") (pin "9") (pinfunction "~{LOAD}_9") (pintype "input"))
    )
    (net (code "135") (name "/{slash}EXAMN") (class "Default")
      (node (ref "IC4") (pin "6") (pinfunction "O_6") (pintype "output"))
      (node (ref "IC5") (pin "9") (pinfunction "I0_9") (pintype "input"))
    )
    (net (code "136") (name "/{slash}IRQ") (class "Default")
      (node (ref "SV11") (pin "34") (pinfunction "34_34") (pintype "passive"))
      (node (ref "SV6") (pin "6") (pinfunction "6_6") (pintype "passive"))
    )
    (net (code "137") (name "/{slash}RESET1") (class "Default")
      (node (ref "SV4") (pin "7") (pinfunction "7_7") (pintype "passive"))
      (node (ref "V1") (pin "1") (pinfunction "~{CLR}_1") (pintype "input"))
      (node (ref "V2") (pin "1") (pinfunction "~{CLR}_1") (pintype "input"))
      (node (ref "V3") (pin "1") (pinfunction "~{CLR}_1") (pintype "input"))
      (node (ref "V4") (pin "1") (pinfunction "~{CLR}_1") (pintype "input"))
    )
    (net (code "138") (name "/{slash}WE") (class "Default")
      (node (ref "SV6") (pin "4") (pinfunction "4_4") (pintype "passive"))
    )
    (net (code "139") (name "/{slash}WR") (class "Default")
      (node (ref "SV4") (pin "8") (pinfunction "8_8") (pintype "passive"))
    )
    (net (code "140") (name "GND") (class "Default")
      (node (ref "C1") (pin "2") (pinfunction "2_2") (pintype "passive"))
      (node (ref "C2") (pin "2") (pinfunction "2_2") (pintype "passive"))
      (node (ref "C3") (pin "2") (pinfunction "2_2") (pintype "passive"))
      (node (ref "C4") (pin "2") (pinfunction "2_2") (pintype "passive"))
      (node (ref "C5") (pin "2") (pinfunction "2_2") (pintype "passive"))
      (node (ref "IC10") (pin "8") (pinfunction "GND_8") (pintype "power_in"))
      (node (ref "IC11") (pin "8") (pinfunction "GND_8") (pintype "power_in"))
      (node (ref "IC12") (pin "8") (pinfunction "GND_8") (pintype "power_in"))
      (node (ref "IC2") (pin "1") (pinfunction "G_1") (pintype "input"))
      (node (ref "SV1") (pin "4") (pinfunction "4_4") (pintype "passive"))
      (node (ref "SV1") (pin "5") (pinfunction "5_5") (pintype "passive"))
      (node (ref "SV1") (pin "6") (pinfunction "6_6") (pintype "passive"))
      (node (ref "SV11") (pin "1") (pinfunction "1_1") (pintype "passive"))
      (node (ref "SV11") (pin "2") (pinfunction "2_2") (pintype "passive"))
      (node (ref "SV11") (pin "27") (pinfunction "27_27") (pintype "passive"))
      (node (ref "SV11") (pin "29") (pinfunction "29_29") (pintype "passive"))
      (node (ref "SV11") (pin "31") (pinfunction "31_31") (pintype "passive"))
      (node (ref "SV11") (pin "33") (pinfunction "33_33") (pintype "passive"))
      (node (ref "SV11") (pin "35") (pinfunction "35_35") (pintype "passive"))
      (node (ref "SV11") (pin "37") (pinfunction "37_37") (pintype "passive"))
      (node (ref "SV3") (pin "4") (pinfunction "4_4") (pintype "passive"))
      (node (ref "SV3") (pin "5") (pinfunction "5_5") (pintype "passive"))
      (node (ref "SV3") (pin "6") (pinfunction "6_6") (pintype "passive"))
    )
    (net (code "141") (name "Net-(IC1A-I)") (class "Default")
      (node (ref "C1") (pin "1") (pinfunction "1_1") (pintype "passive"))
      (node (ref "IC1") (pin "13") (pinfunction "I_13") (pintype "input"))
      (node (ref "R2") (pin "2") (pinfunction "2_2") (pintype "passive"))
    )
    (net (code "142") (name "Net-(IC1B-I)") (class "Default")
      (node (ref "C2") (pin "1") (pinfunction "1_1") (pintype "passive"))
      (node (ref "IC1") (pin "11") (pinfunction "I_11") (pintype "input"))
      (node (ref "R4") (pin "2") (pinfunction "2_2") (pintype "passive"))
    )
    (net (code "143") (name "Net-(IC1C-I)") (class "Default")
      (node (ref "C3") (pin "1") (pinfunction "1_1") (pintype "passive"))
      (node (ref "IC1") (pin "9") (pinfunction "I_9") (pintype "input"))
      (node (ref "R6") (pin "2") (pinfunction "2_2") (pintype "passive"))
    )
    (net (code "144") (name "Net-(IC1D-I)") (class "Default")
      (node (ref "C4") (pin "1") (pinfunction "1_1") (pintype "passive"))
      (node (ref "IC1") (pin "1") (pinfunction "I_1") (pintype "input"))
      (node (ref "R8") (pin "2") (pinfunction "2_2") (pintype "passive"))
    )
    (net (code "145") (name "Net-(IC5A-O)") (class "Default")
      (node (ref "IC5") (pin "3") (pinfunction "O_3") (pintype "output"))
      (node (ref "IC5") (pin "4") (pinfunction "I0_4") (pintype "input"))
    )
    (net (code "146") (name "VCC") (class "Default")
      (node (ref "R1") (pin "1") (pinfunction "1_1") (pintype "passive"))
      (node (ref "R10") (pin "2") (pinfunction "2_2") (pintype "passive"))
      (node (ref "R3") (pin "1") (pinfunction "1_1") (pintype "passive"))
      (node (ref "R5") (pin "1") (pinfunction "1_1") (pintype "passive"))
      (node (ref "R7") (pin "1") (pinfunction "1_1") (pintype "passive"))
      (node (ref "R9") (pin "2") (pinfunction "2_2") (pintype "passive"))
      (node (ref "SV1") (pin "1") (pinfunction "1_1") (pintype "passive"))
      (node (ref "SV1") (pin "2") (pinfunction "2_2") (pintype "passive"))
      (node (ref "SV11") (pin "39") (pinfunction "39_39") (pintype "passive"))
      (node (ref "SV11") (pin "40") (pinfunction "40_40") (pintype "passive"))
      (node (ref "SV3") (pin "1") (pinfunction "1_1") (pintype "passive"))
      (node (ref "SV3") (pin "2") (pinfunction "2_2") (pintype "passive"))
      (node (ref "SV3") (pin "3") (pinfunction "3_3") (pintype "passive"))
      (node (ref "V1") (pin "10") (pinfunction "ENT_10") (pintype "input"))
    )
    (net (code "147") (name "unconnected-(IC10-CD+-Pad9)") (class "Default")
      (node (ref "IC10") (pin "9") (pinfunction "CD+_9") (pintype "passive"))
    )
    (net (code "148") (name "unconnected-(IC11-CD+-Pad9)") (class "Default")
      (node (ref "IC11") (pin "9") (pinfunction "CD+_9") (pintype "passive"))
    )
    (net (code "149") (name "unconnected-(IC12-CD+-Pad9)") (class "Default")
      (node (ref "IC12") (pin "9") (pinfunction "CD+_9") (pintype "passive"))
    )
    (net (code "150") (name "unconnected-(IC12-I3-Pad3)") (class "Default")
      (node (ref "IC12") (pin "3") (pinfunction "I3_3") (pintype "input"))
    )
    (net (code "151") (name "unconnected-(IC12-I4-Pad4)") (class "Default")
      (node (ref "IC12") (pin "4") (pinfunction "I4_4") (pintype "input"))
    )
    (net (code "152") (name "unconnected-(IC12-I5-Pad5)") (class "Default")
      (node (ref "IC12") (pin "5") (pinfunction "I5_5") (pintype "input"))
    )
    (net (code "153") (name "unconnected-(IC12-I6-Pad6)") (class "Default")
      (node (ref "IC12") (pin "6") (pinfunction "I6_6") (pintype "input"))
    )
    (net (code "154") (name "unconnected-(IC12-I7-Pad7)") (class "Default")
      (node (ref "IC12") (pin "7") (pinfunction "I7_7") (pintype "input"))
    )
    (net (code "155") (name "unconnected-(IC12-O3-Pad14)") (class "Default")
      (node (ref "IC12") (pin "14") (pinfunction "O3_14") (pintype "open_collector"))
    )
    (net (code "156") (name "unconnected-(IC12-O4-Pad13)") (class "Default")
      (node (ref "IC12") (pin "13") (pinfunction "O4_13") (pintype "open_collector"))
    )
    (net (code "157") (name "unconnected-(IC12-O5-Pad12)") (class "Default")
      (node (ref "IC12") (pin "12") (pinfunction "O5_12") (pintype "open_collector"))
    )
    (net (code "158") (name "unconnected-(IC12-O6-Pad11)") (class "Default")
      (node (ref "IC12") (pin "11") (pinfunction "O6_11") (pintype "open_collector"))
    )
    (net (code "159") (name "unconnected-(IC12-O7-Pad10)") (class "Default")
      (node (ref "IC12") (pin "10") (pinfunction "O7_10") (pintype "open_collector"))
    )
    (net (code "160") (name "unconnected-(SV10-Pad1)") (class "Default")
      (node (ref "SV10") (pin "1") (pinfunction "1_1") (pintype "passive"))
    )
    (net (code "161") (name "unconnected-(SV10-Pad2)") (class "Default")
      (node (ref "SV10") (pin "2") (pinfunction "2_2") (pintype "passive"))
    )
    (net (code "162") (name "unconnected-(SV10-Pad3)") (class "Default")
      (node (ref "SV10") (pin "3") (pinfunction "3_3") (pintype "passive"))
    )
    (net (code "163") (name "unconnected-(SV10-Pad4)") (class "Default")
      (node (ref "SV10") (pin "4") (pinfunction "4_4") (pintype "passive"))
    )
    (net (code "164") (name "unconnected-(SV10-Pad5)") (class "Default")
      (node (ref "SV10") (pin "5") (pinfunction "5_5") (pintype "passive"))
    )
    (net (code "165") (name "unconnected-(SV10-Pad6)") (class "Default")
      (node (ref "SV10") (pin "6") (pinfunction "6_6") (pintype "passive"))
    )
    (net (code "166") (name "unconnected-(SV10-Pad7)") (class "Default")
      (node (ref "SV10") (pin "7") (pinfunction "7_7") (pintype "passive"))
    )
    (net (code "167") (name "unconnected-(SV10-Pad8)") (class "Default")
      (node (ref "SV10") (pin "8") (pinfunction "8_8") (pintype "passive"))
    )
    (net (code "168") (name "unconnected-(SV10-Pad9)") (class "Default")
      (node (ref "SV10") (pin "9") (pinfunction "9_9") (pintype "passive"))
    )
    (net (code "169") (name "unconnected-(SV10-Pad10)") (class "Default")
      (node (ref "SV10") (pin "10") (pinfunction "10_10") (pintype "passive"))
    )
    (net (code "170") (name "unconnected-(SV10-Pad11)") (class "Default")
      (node (ref "SV10") (pin "11") (pinfunction "11_11") (pintype "passive"))
    )
    (net (code "171") (name "unconnected-(SV10-Pad12)") (class "Default")
      (node (ref "SV10") (pin "12") (pinfunction "12_12") (pintype "passive"))
    )
    (net (code "172") (name "unconnected-(SV10-Pad13)") (class "Default")
      (node (ref "SV10") (pin "13") (pinfunction "13_13") (pintype "passive"))
    )
    (net (code "173") (name "unconnected-(SV10-Pad14)") (class "Default")
      (node (ref "SV10") (pin "14") (pinfunction "14_14") (pintype "passive"))
    )
    (net (code "174") (name "unconnected-(SV10-Pad15)") (class "Default")
      (node (ref "SV10") (pin "15") (pinfunction "15_15") (pintype "passive"))
    )
    (net (code "175") (name "unconnected-(SV10-Pad16)") (class "Default")
      (node (ref "SV10") (pin "16") (pinfunction "16_16") (pintype "passive"))
    )
    (net (code "176") (name "unconnected-(SV10-Pad17)") (class "Default")
      (node (ref "SV10") (pin "17") (pinfunction "17_17") (pintype "passive"))
    )
    (net (code "177") (name "unconnected-(SV10-Pad18)") (class "Default")
      (node (ref "SV10") (pin "18") (pinfunction "18_18") (pintype "passive"))
    )
    (net (code "178") (name "unconnected-(SV10-Pad19)") (class "Default")
      (node (ref "SV10") (pin "19") (pinfunction "19_19") (pintype "passive"))
    )
    (net (code "179") (name "unconnected-(SV10-Pad20)") (class "Default")
      (node (ref "SV10") (pin "20") (pinfunction "20_20") (pintype "passive"))
    )
    (net (code "180") (name "unconnected-(SV10-Pad21)") (class "Default")
      (node (ref "SV10") (pin "21") (pinfunction "21_21") (pintype "passive"))
    )
    (net (code "181") (name "unconnected-(SV10-Pad22)") (class "Default")
      (node (ref "SV10") (pin "22") (pinfunction "22_22") (pintype "passive"))
    )
    (net (code "182") (name "unconnected-(SV10-Pad23)") (class "Default")
      (node (ref "SV10") (pin "23") (pinfunction "23_23") (pintype "passive"))
    )
    (net (code "183") (name "unconnected-(SV10-Pad24)") (class "Default")
      (node (ref "SV10") (pin "24") (pinfunction "24_24") (pintype "passive"))
    )
    (net (code "184") (name "unconnected-(SV10-Pad25)") (class "Default")
      (node (ref "SV10") (pin "25") (pinfunction "25_25") (pintype "passive"))
    )
    (net (code "185") (name "unconnected-(SV10-Pad26)") (class "Default")
      (node (ref "SV10") (pin "26") (pinfunction "26_26") (pintype "passive"))
    )
    (net (code "186") (name "unconnected-(SV10-Pad27)") (class "Default")
      (node (ref "SV10") (pin "27") (pinfunction "27_27") (pintype "passive"))
    )
    (net (code "187") (name "unconnected-(SV10-Pad28)") (class "Default")
      (node (ref "SV10") (pin "28") (pinfunction "28_28") (pintype "passive"))
    )
    (net (code "188") (name "unconnected-(SV10-Pad29)") (class "Default")
      (node (ref "SV10") (pin "29") (pinfunction "29_29") (pintype "passive"))
    )
    (net (code "189") (name "unconnected-(SV10-Pad30)") (class "Default")
      (node (ref "SV10") (pin "30") (pinfunction "30_30") (pintype "passive"))
    )
    (net (code "190") (name "unconnected-(SV10-Pad31)") (class "Default")
      (node (ref "SV10") (pin "31") (pinfunction "31_31") (pintype "passive"))
    )
    (net (code "191") (name "unconnected-(SV10-Pad32)") (class "Default")
      (node (ref "SV10") (pin "32") (pinfunction "32_32") (pintype "passive"))
    )
    (net (code "192") (name "unconnected-(SV10-Pad33)") (class "Default")
      (node (ref "SV10") (pin "33") (pinfunction "33_33") (pintype "passive"))
    )
    (net (code "193") (name "unconnected-(SV10-Pad34)") (class "Default")
      (node (ref "SV10") (pin "34") (pinfunction "34_34") (pintype "passive"))
    )
    (net (code "194") (name "unconnected-(SV10-Pad35)") (class "Default")
      (node (ref "SV10") (pin "35") (pinfunction "35_35") (pintype "passive"))
    )
    (net (code "195") (name "unconnected-(SV10-Pad36)") (class "Default")
      (node (ref "SV10") (pin "36") (pinfunction "36_36") (pintype "passive"))
    )
    (net (code "196") (name "unconnected-(SV10-Pad37)") (class "Default")
      (node (ref "SV10") (pin "37") (pinfunction "37_37") (pintype "passive"))
    )
    (net (code "197") (name "unconnected-(SV10-Pad38)") (class "Default")
      (node (ref "SV10") (pin "38") (pinfunction "38_38") (pintype "passive"))
    )
    (net (code "198") (name "unconnected-(SV10-Pad39)") (class "Default")
      (node (ref "SV10") (pin "39") (pinfunction "39_39") (pintype "passive"))
    )
    (net (code "199") (name "unconnected-(SV10-Pad40)") (class "Default")
      (node (ref "SV10") (pin "40") (pinfunction "40_40") (pintype "passive"))
    )
    (net (code "200") (name "unconnected-(SV12-Pad3)") (class "Default")
      (node (ref "SV12") (pin "3") (pinfunction "3_3") (pintype "passive"))
    )
    (net (code "201") (name "unconnected-(SV12-Pad4)") (class "Default")
      (node (ref "SV12") (pin "4") (pinfunction "4_4") (pintype "passive"))
    )
    (net (code "202") (name "unconnected-(SV12-Pad5)") (class "Default")
      (node (ref "SV12") (pin "5") (pinfunction "5_5") (pintype "passive"))
    )
    (net (code "203") (name "unconnected-(SV12-Pad6)") (class "Default")
      (node (ref "SV12") (pin "6") (pinfunction "6_6") (pintype "passive"))
    )
    (net (code "204") (name "unconnected-(V4C-RCO-Pad15)") (class "Default")
      (node (ref "V4") (pin "15") (pinfunction "RCO_15") (pintype "output"))
    )
  )
)
